# AnalogMux.net
KiCad netlist of a schematic drawn in Altium Designer
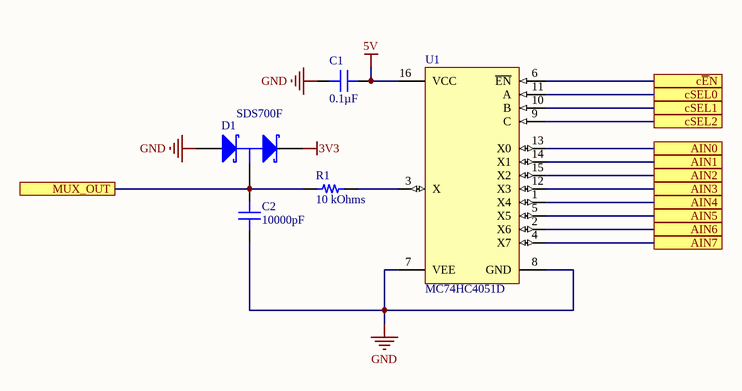
[diagram p0: AnalogMux.SchDoc]

(export (version "E")
  (design (tool "Eeschema 10.0.6"))
  (components
    (comp (ref "C1")
      (value "0.1µF")
      (footprint "CAP 0805_2012")
      (description "CAP CER 0.1UF 50V X7R 0805")
      (fields (field (name "PART NUMBER") "CC0805MRX7R9BB104") (field (name "MANUFACTURER") "Yageo"))
      (libsource (lib "Celestial Altium Library - altium_library") (part "Capacitor"))
    )
    (comp (ref "C2")
      (value "10000pF")
      (footprint "CAP 0805_2012")
      (description "CAP CER 0805 10NF 50V X7R 10%")
      (fields (field (name "PART NUMBER") "C0805C103K5RECAUTO") (field (name "MANUFACTURER") "KEMET"))
      (libsource (lib "Celestial Altium Library - altium_library") (part "Capacitor"))
    )
    (comp (ref "D1")
      (value "SDS700F")
      (footprint "SOT323_N")
      (description "Schottky Barrier Double Diode")
      (fields (field (name "PUBLISHER") "Altium Limited"))
      (libsource (lib "Philips Discrete Diode - Schottky") (part "BAT854SW"))
    )
    (comp (ref "R1")
      (value "10 kOhms")
      (footprint "RES 0805_2012")
      (description "RES 10K OHM 0.1% 1/10W 0805")
      (fields
        (field (name "PART NUMBER") "RNCS0805BKE10K0")
        (field (name "MANUFACTURER") "Stackpole Electronics Inc")
      )
      (libsource (lib "Celestial Altium Library - altium_library") (part "Resistor"))
    )
    (comp (ref "U1")
      (value "MC74HC4051D")
      (footprint "751B-05_N")
      (description "8-Channel Analog Multiplexer/Demultiplexer")
      (fields (field (name "PUBLISHER") "Altium Limited"))
      (libsource (lib "ON Semi Logic Multiplexer") (part "MC74HC4051D"))
    )
  )
  (nets
    (net (code "1") (name "/AIN0") (class "Default")
      (node (ref "U1") (pin "13") (pinfunction "X0_13") (pintype "bidirectional"))
    )
    (net (code "2") (name "/AIN1") (class "Default")
      (node (ref "U1") (pin "14") (pinfunction "X1_14") (pintype "bidirectional"))
    )
    (net (code "3") (name "/AIN2") (class "Default")
      (node (ref "U1") (pin "15") (pinfunction "X2_15") (pintype "bidirectional"))
    )
    (net (code "4") (name "/AIN3") (class "Default")
      (node (ref "U1") (pin "12") (pinfunction "X3_12") (pintype "bidirectional"))
    )
    (net (code "5") (name "/AIN4") (class "Default")
      (node (ref "U1") (pin "1") (pinfunction "X4_1") (pintype "bidirectional"))
    )
    (net (code "6") (name "/AIN5") (class "Default")
      (node (ref "U1") (pin "5") (pinfunction "X5_5") (pintype "bidirectional"))
    )
    (net (code "7") (name "/AIN6") (class "Default")
      (node (ref "U1") (pin "2") (pinfunction "X6_2") (pintype "bidirectional"))
    )
    (net (code "8") (name "/AIN7") (class "Default")
      (node (ref "U1") (pin "4") (pinfunction "X7_4") (pintype "bidirectional"))
    )
    (net (code "9") (name "/MUX_OUT") (class "Default")
      (node (ref "C2") (pin "2") (pinfunction "2_2") (pintype "passive"))
      (node (ref "D1") (pin "3") (pinfunction "C_3") (pintype "passive"))
      (node (ref "R1") (pin "1") (pinfunction "1_1") (pintype "passive"))
    )
    (net (code "10") (name "/cSEL0") (class "Default")
      (node (ref "U1") (pin "11") (pinfunction "A_11") (pintype "input"))
    )
    (net (code "11") (name "/cSEL1") (class "Default")
      (node (ref "U1") (pin "10") (pinfunction "B_10") (pintype "input"))
    )
    (net (code "12") (name "/cSEL2") (class "Default")
      (node (ref "U1") (pin "9") (pinfunction "C_9") (pintype "input"))
    )
    (net (code "13") (name "/c~{E}N") (class "Default")
      (node (ref "U1") (pin "6") (pinfunction "~{EN}_6") (pintype "input"))
    )
    (net (code "14") (name "3V3") (class "Default")
      (node (ref "D1") (pin "2") (pinfunction "K_2") (pintype "passive"))
    )
    (net (code "15") (name "5V") (class "Default")
      (node (ref "C1") (pin "1") (pinfunction "1_1") (pintype "passive"))
      (node (ref "U1") (pin "16") (pinfunction "VCC_16") (pintype "power_in"))
    )
    (net (code "16") (name "GND") (class "Default")
      (node (ref "C1") (pin "2") (pinfunction "2_2") (pintype "passive"))
      (node (ref "C2") (pin "1") (pinfunction "1_1") (pintype "passive"))
      (node (ref "D1") (pin "1") (pinfunction "A_1") (pintype "passive"))
      (node (ref "U1") (pin "7") (pinfunction "VEE_7") (pintype "power_in"))
      (node (ref "U1") (pin "8") (pinfunction "GND_8") (pintype "power_in"))
    )
    (net (code "17") (name "Net-(U1-X)") (class "Default")
      (node (ref "R1") (pin "2") (pinfunction "2_2") (pintype "passive"))
      (node (ref "U1") (pin "3") (pinfunction "X_3") (pintype "bidirectional"))
    )
  )
)
